# Power.net
KiCad netlist of a schematic drawn in Altium Designer
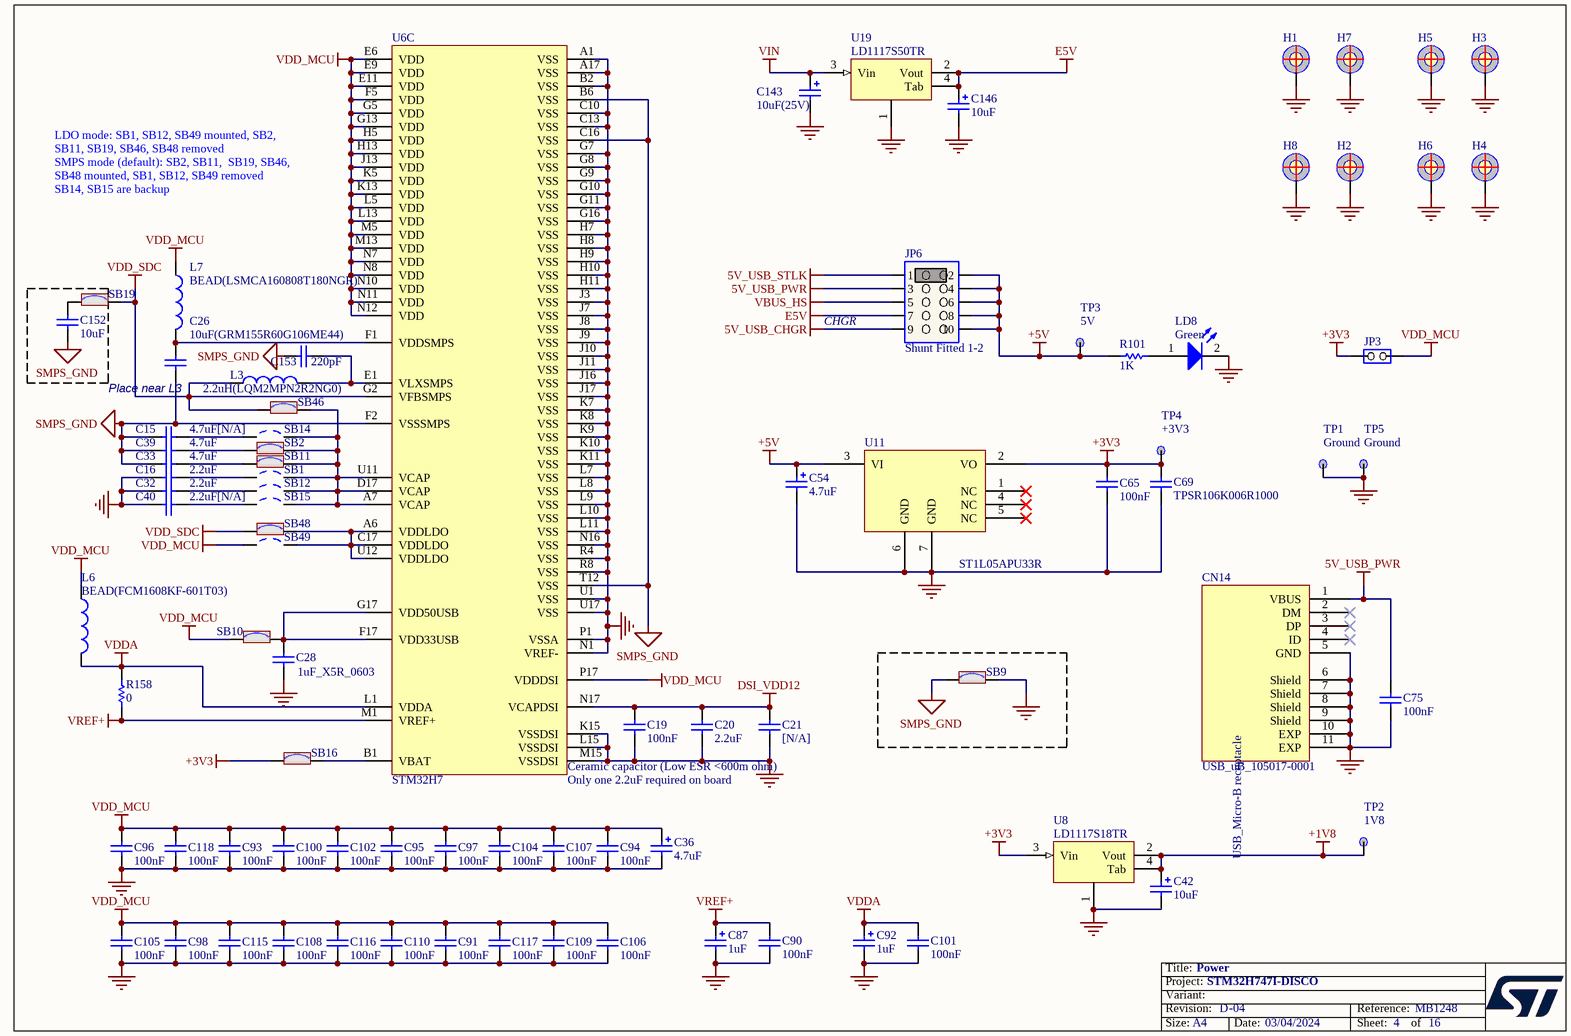
[diagram p0: Power.SchDoc]

(export (version "E")
  (design (tool "Eeschema 10.0.6"))
  (components
    (comp (ref "C15")
      (value "4.7uF[N/A]")
      (footprint "0402C")
      (description "Capacitor")
      (fields (field (name "PUBLISHER") "Altium Limited"))
      (libsource (lib "Miscellaneous Devices") (part "cap"))
    )
    (comp (ref "C16")
      (value "2.2uF")
      (footprint "0603C")
      (description "Capacitor")
      (fields (field (name "PUBLISHER") "Altium Limited"))
      (libsource (lib "Miscellaneous Devices") (part "Cap"))
    )
    (comp (ref "C19")
      (value "100nF")
      (footprint "0402C")
      (description "Capacitor")
      (fields (field (name "PUBLISHER") "Altium Limited"))
      (libsource (lib "Miscellaneous Devices") (part "CAP"))
    )
    (comp (ref "C20")
      (value "2.2uF")
      (footprint "0603C")
      (description "Capacitor")
      (fields (field (name "PUBLISHER") "Altium Limited"))
      (libsource (lib "Miscellaneous Devices") (part "CAP"))
    )
    (comp (ref "C21")
      (value "[N/A]")
      (footprint "1206C")
      (description "Capacitor")
      (fields (field (name "PUBLISHER") "Altium Limited"))
      (libsource (lib "Miscellaneous Devices") (part "cap"))
    )
    (comp (ref "C26")
      (value "10uF(GRM155R60G106ME44)")
      (footprint "0402C")
      (description "Capacitor")
      (fields (field (name "PUBLISHER") "Altium Limited"))
      (libsource (lib "Miscellaneous Devices") (part "Cap"))
    )
    (comp (ref "C28")
      (value "1uF_X5R_0603")
      (footprint "0603C")
      (description "0603  X5R 1礔")
      (fields (field (name "TOLERANCE") "10%"))
      (libsource (lib "MB963_1") (part "CAP SMD 0603  X5R 1礔 25V 10%"))
    )
    (comp (ref "C32")
      (value "2.2uF")
      (footprint "0603C")
      (description "Capacitor")
      (fields (field (name "PUBLISHER") "Altium Limited"))
      (libsource (lib "Miscellaneous Devices") (part "Cap"))
    )
    (comp (ref "C33")
      (value "4.7uF")
      (footprint "0402C")
      (description "Capacitor")
      (fields (field (name "PUBLISHER") "Altium Limited"))
      (libsource (lib "Miscellaneous Devices") (part "Cap"))
    )
    (comp (ref "C36")
      (value "4.7uF")
      (footprint "TAN-A")
      (description "Polarized Capacitor (Radial)")
      (fields (field (name "PUBLISHER") "Altium Limited"))
      (libsource (lib "Miscellaneous Devices") (part "Cap Pol1"))
    )
    (comp (ref "C39")
      (value "4.7uF")
      (footprint "0402C")
      (description "Capacitor")
      (fields (field (name "PUBLISHER") "Altium Limited"))
      (libsource (lib "Miscellaneous Devices") (part "Cap"))
    )
    (comp (ref "C40")
      (value "2.2uF[N/A]")
      (footprint "0603C")
      (description "Capacitor")
      (fields (field (name "PUBLISHER") "Altium Limited"))
      (libsource (lib "Miscellaneous Devices") (part "Cap"))
    )
    (comp (ref "C42")
      (value "10uF")
      (footprint "TAN-A")
      (description "Polarized Capacitor,10uF,10V,10%,typeA,VISHAY")
      (libsource (lib "MCD_TOOLS") (part "Cap_10uF_POL_10%_TANA"))
    )
    (comp (ref "C54")
      (value "4.7uF")
      (footprint "TAN-A")
      (description "Polarized Capacitor (Radial)")
      (fields (field (name "PUBLISHER") "Altium Limited"))
      (libsource (lib "*") (part "Cap Pol1"))
    )
    (comp (ref "C65")
      (value "100nF")
      (footprint "0603C")
      (description "Capacitor")
      (fields (field (name "PUBLISHER") "Altium Limited"))
      (libsource (lib "Miscellaneous Devices") (part "Cap"))
    )
    (comp (ref "C69")
      (value "TPSR106K006R1000")
      (footprint "0805C")
      (description "Capacitor")
      (libsource (lib "Miscellaneous Devices") (part "Cap"))
    )
    (comp (ref "C75")
      (value "100nF")
      (footprint "0402C")
      (description "Capacitor,20pF,50V,NPO,5%,0402")
      (fields
        (field (name "INTERNAL_PART_NUMBER") "MCD-00016")
        (field (name "MANUFACTURER_PART_NUMBER") "CC0402JRNPO9BN200")
        (field (name "PROVIDED_BY") "Subcon")
      )
      (libsource (lib "MCD_PARTS_database") (part "Capacitor"))
    )
    (comp (ref "C87")
      (value "1uF")
      (footprint "TAN-A")
      (description "Polarized Capacitor (Radial)")
      (fields (field (name "PUBLISHER") "Altium Limited"))
      (libsource (lib "Miscellaneous Devices") (part "Cap Pol1"))
    )
    (comp (ref "C90")
      (value "100nF")
      (footprint "0402C")
      (description "Capacitor")
      (fields (field (name "PUBLISHER") "Altium Limited"))
      (libsource (lib "Miscellaneous Devices") (part "Cap"))
    )
    (comp (ref "C91")
      (value "100nF")
      (footprint "0402C")
      (description "Capacitor")
      (fields (field (name "PUBLISHER") "Altium Limited"))
      (libsource (lib "Miscellaneous Devices") (part "CAP"))
    )
    (comp (ref "C92")
      (value "1uF")
      (footprint "TAN-A")
      (description "Polarized Capacitor (Radial)")
      (fields (field (name "PUBLISHER") "Altium Limited"))
      (libsource (lib "Miscellaneous Devices") (part "Cap Pol1"))
    )
    (comp (ref "C93")
      (value "100nF")
      (footprint "0402C")
      (description "Capacitor")
      (fields (field (name "PUBLISHER") "Altium Limited"))
      (libsource (lib "Miscellaneous Devices") (part "CAP"))
    )
    (comp (ref "C94")
      (value "100nF")
      (footprint "0402C")
      (description "Capacitor")
      (fields (field (name "PUBLISHER") "Altium Limited"))
      (libsource (lib "Miscellaneous Devices") (part "CAP"))
    )
    (comp (ref "C95")
      (value "100nF")
      (footprint "0402C")
      (description "Capacitor")
      (fields (field (name "PUBLISHER") "Altium Limited"))
      (libsource (lib "Miscellaneous Devices") (part "CAP"))
    )
    (comp (ref "C96")
      (value "100nF")
      (footprint "0402C")
      (description "Capacitor")
      (fields (field (name "PUBLISHER") "Altium Limited"))
      (libsource (lib "Miscellaneous Devices") (part "CAP"))
    )
    (comp (ref "C97")
      (value "100nF")
      (footprint "0402C")
      (description "Capacitor")
      (fields (field (name "PUBLISHER") "Altium Limited"))
      (libsource (lib "Miscellaneous Devices") (part "CAP"))
    )
    (comp (ref "C98")
      (value "100nF")
      (footprint "0402C")
      (description "Capacitor")
      (fields (field (name "PUBLISHER") "Altium Limited"))
      (libsource (lib "Miscellaneous Devices") (part "CAP"))
    )
    (comp (ref "C100")
      (value "100nF")
      (footprint "0402C")
      (description "Capacitor")
      (fields (field (name "PUBLISHER") "Altium Limited"))
      (libsource (lib "Miscellaneous Devices") (part "CAP"))
    )
    (comp (ref "C101")
      (value "100nF")
      (footprint "0402C")
      (description "Capacitor")
      (fields (field (name "PUBLISHER") "Altium Limited"))
      (libsource (lib "Miscellaneous Devices") (part "Cap"))
    )
    (comp (ref "C102")
      (value "100nF")
      (footprint "0402C")
      (description "Capacitor")
      (fields (field (name "PUBLISHER") "Altium Limited"))
      (libsource (lib "Miscellaneous Devices") (part "CAP"))
    )
    (comp (ref "C104")
      (value "100nF")
      (footprint "0402C")
      (description "Capacitor")
      (fields (field (name "PUBLISHER") "Altium Limited"))
      (libsource (lib "Miscellaneous Devices") (part "CAP"))
    )
    (comp (ref "C105")
      (value "100nF")
      (footprint "0402C")
      (description "Capacitor")
      (fields (field (name "PUBLISHER") "Altium Limited"))
      (libsource (lib "Miscellaneous Devices") (part "CAP"))
    )
    (comp (ref "C106")
      (value "100nF")
      (footprint "0402C")
      (description "Capacitor")
      (fields (field (name "PUBLISHER") "Altium Limited"))
      (libsource (lib "Miscellaneous Devices") (part "CAP"))
    )
    (comp (ref "C107")
      (value "100nF")
      (footprint "0402C")
      (description "Capacitor")
      (fields (field (name "PUBLISHER") "Altium Limited"))
      (libsource (lib "Miscellaneous Devices") (part "CAP"))
    )
    (comp (ref "C108")
      (value "100nF")
      (footprint "0402C")
      (description "Capacitor")
      (fields (field (name "PUBLISHER") "Altium Limited"))
      (libsource (lib "Miscellaneous Devices") (part "CAP"))
    )
    (comp (ref "C109")
      (value "100nF")
      (footprint "0402C")
      (description "Capacitor")
      (fields (field (name "PUBLISHER") "Altium Limited"))
      (libsource (lib "Miscellaneous Devices") (part "CAP"))
    )
    (comp (ref "C110")
      (value "100nF")
      (footprint "0402C")
      (description "Capacitor")
      (fields (field (name "PUBLISHER") "Altium Limited"))
      (libsource (lib "Miscellaneous Devices") (part "CAP"))
    )
    (comp (ref "C115")
      (value "100nF")
      (footprint "0402C")
      (description "Capacitor")
      (fields (field (name "PUBLISHER") "Altium Limited"))
      (libsource (lib "Miscellaneous Devices") (part "CAP"))
    )
    (comp (ref "C116")
      (value "100nF")
      (footprint "0402C")
      (description "Capacitor")
      (fields (field (name "PUBLISHER") "Altium Limited"))
      (libsource (lib "Miscellaneous Devices") (part "CAP"))
    )
    (comp (ref "C117")
      (value "100nF")
      (footprint "0402C")
      (description "Capacitor")
      (fields (field (name "PUBLISHER") "Altium Limited"))
      (libsource (lib "Miscellaneous Devices") (part "CAP"))
    )
    (comp (ref "C118")
      (value "100nF")
      (footprint "0402C")
      (description "Capacitor")
      (fields (field (name "PUBLISHER") "Altium Limited"))
      (libsource (lib "Miscellaneous Devices") (part "CAP"))
    )
    (comp (ref "C143")
      (value "10uF(25V)")
      (footprint "TAN-B")
      (description "Polarized Capacitor (Radial)")
      (fields (field (name "PUBLISHER") "Altium Limited"))
      (libsource (lib "Miscellaneous Devices") (part "Cap Pol1"))
    )
    (comp (ref "C146")
      (value "10uF")
      (footprint "TAN-A")
      (description "Polarized Capacitor,10uF,10V,10%,typeA,VISHAY")
      (libsource (lib "MCD_TOOLS") (part "Cap_10uF_POL_10%_TANA"))
    )
    (comp (ref "C152")
      (value "10uF")
      (footprint "0603C")
      (description "Capacitor")
      (fields (field (name "PUBLISHER") "Altium Limited"))
      (libsource (lib "Miscellaneous Devices") (part "Cap"))
    )
    (comp (ref "C153")
      (value "220pF")
      (footprint "0402C")
      (description "Capacitor")
      (fields (field (name "PUBLISHER") "Altium Limited"))
      (libsource (lib "Miscellaneous Devices") (part "Cap"))
    )
    (comp (ref "CN14")
      (value "USB_uB_105017-0001")
      (footprint "MICRO_USB_B_105017")
      (description "USB-MICRO-B, 0.65mm, RA, SMT, Bottom Mount,")
      (fields
        (field (name "INTERNAL_PART_NUMBER") "MCD-00028")
        (field (name "MANUFACTURER_PART_NUMBER") "1050170001")
        (field (name "PROVIDED_BY") "Subcon")
      )
      (libsource (lib "MCD_PARTS_database") (part "USB_uB_105017.0001"))
    )
    (comp (ref "H1")
      (value "POSITION HOLE C6D3R5")
      (footprint "HOLE_C7D3R5")
      (libsource (lib "MCD_TOOLS_MISCELLANEOUS") (part "POSITION HOLE C6D3R5"))
    )
    (comp (ref "H2")
      (value "POSITION HOLE C6D3R5")
      (footprint "HOLE_C7D3R5")
      (libsource (lib "MCD_TOOLS_MISCELLANEOUS") (part "POSITION HOLE C6D3R5"))
    )
    (comp (ref "H3")
      (value "POSITION HOLE C6D3R5")
      (footprint "HOLE_C9D4R5")
      (libsource (lib "MCD_TOOLS_MISCELLANEOUS") (part "POSITION HOLE C6D3R5"))
    )
    (comp (ref "H4")
      (value "POSITION HOLE C6D3R5")
      (footprint "HOLE_C9D4R5")
      (libsource (lib "MCD_TOOLS_MISCELLANEOUS") (part "POSITION HOLE C6D3R5"))
    )
    (comp (ref "H5")
      (value "POSITION HOLE C6D3R5")
      (footprint "HOLE_C9D4R5")
      (libsource (lib "MCD_TOOLS_MISCELLANEOUS") (part "POSITION HOLE C6D3R5"))
    )
    (comp (ref "H6")
      (value "POSITION HOLE C6D3R5")
      (footprint "HOLE_C9D4R5")
      (libsource (lib "MCD_TOOLS_MISCELLANEOUS") (part "POSITION HOLE C6D3R5"))
    )
    (comp (ref "H7")
      (value "POSITION HOLE C6D3R5")
      (footprint "HOLE_C7D3R5")
      (libsource (lib "MCD_TOOLS_MISCELLANEOUS") (part "POSITION HOLE C6D3R5"))
    )
    (comp (ref "H8")
      (value "POSITION HOLE C6D3R5")
      (footprint "HOLE_C7D3R5")
      (libsource (lib "MCD_TOOLS_MISCELLANEOUS") (part "POSITION HOLE C6D3R5"))
    )
    (comp (ref "JP3") (value "~") (footprint "SIP2") (libsource (lib "*") (part "JP2")))
    (comp (ref "JP6")
      (value "Shunt Fitted 1-2")
      (footprint "HDR_2X5_2R54")
      (description "Header, 5x2, 2,54mm, VR, TH, Height 5.84mm/2.54mm - Shunt Fitted 1-2")
      (fields
        (field (name "INTERNAL_PART_NUMBER") "MCD-01203")
        (field (name "MANUFACTURER_PART_NUMBER") "TSW-105-07-x-D")
        (field (name "PROVIDED_BY") "Subcon")
      )
      (libsource (lib "MCD_PARTS_database") (part "Jumper_Header 5x2 Fitted 1-2"))
    )
    (comp (ref "L3")
      (value "2.2uH(LQM2MPN2R2NG0)")
      (footprint "LSM2_VLS2016E_S")
      (description "Inductor")
      (fields (field (name "PUBLISHER") "Altium Limited"))
      (libsource (lib "Miscellaneous Devices") (part "Inductor"))
    )
    (comp (ref "L6")
      (value "BEAD(FCM1608KF-601T03)")
      (footprint "0603L")
      (description "Inductor")
      (fields (field (name "PUBLISHER") "Altium Limited"))
      (libsource (lib "Miscellaneous Devices") (part "Inductor"))
    )
    (comp (ref "L7")
      (value "BEAD(LSMCA160808T180NGR)")
      (footprint "0603L")
      (description "Inductor")
      (fields (field (name "MPN") "LSMCA160808T180NGR") (field (name "PUBLISHER") "Altium Limited"))
      (libsource (lib "Miscellaneous Devices") (part "Inductor"))
    )
    (comp (ref "LD8")
      (value "Green")
      (footprint "0603D")
      (description "Typical RED, GREEN, YELLOW, AMBER GaAs LED")
      (fields (field (name "PUBLISHER") "Altium Limited"))
      (libsource (lib "Miscellaneous Devices") (part "LED2"))
    )
    (comp (ref "R101")
      (value "1K")
      (footprint "0603R")
      (description "Resistor")
      (fields (field (name "PUBLISHER") "Altium Limited"))
      (libsource (lib "Miscellaneous Devices") (part "res1"))
    )
    (comp (ref "R158")
      (value "0")
      (footprint "0603R")
      (description "Resistor")
      (fields (field (name "PUBLISHER") "Altium Limited"))
      (libsource (lib "Miscellaneous Devices") (part "Res1"))
    )
    (comp (ref "SB1")
      (value "Solder Bridge OFF")
      (footprint "SB_0603")
      (libsource (lib "MCD_TOOLS") (part "SB_OFF"))
    )
    (comp (ref "SB2")
      (value "Solder Bridge ON")
      (footprint "SB_0603")
      (libsource (lib "MCD_TOOLS") (part "SB_ON"))
    )
    (comp (ref "SB9")
      (value "Solder Bridge ON")
      (footprint "SB_0603")
      (libsource (lib "MCD_TOOLS") (part "SB_ON"))
    )
    (comp (ref "SB10")
      (value "Solder Bridge ON")
      (footprint "SB_0603")
      (libsource (lib "MCD_TOOLS") (part "SB_ON"))
    )
    (comp (ref "SB11")
      (value "Solder Bridge ON")
      (footprint "SB_0603")
      (libsource (lib "MCD_TOOLS") (part "SB_ON"))
    )
    (comp (ref "SB12")
      (value "Solder Bridge OFF")
      (footprint "SB_0603")
      (libsource (lib "MCD_TOOLS") (part "SB_OFF"))
    )
    (comp (ref "SB14")
      (value "Solder Bridge OFF")
      (footprint "SB_0603")
      (libsource (lib "MCD_TOOLS") (part "SB_OFF"))
    )
    (comp (ref "SB15")
      (value "Solder Bridge OFF")
      (footprint "SB_0603")
      (libsource (lib "MCD_TOOLS") (part "SB_OFF"))
    )
    (comp (ref "SB16")
      (value "Solder Bridge ON")
      (footprint "SB_0603")
      (libsource (lib "MCD_TOOLS") (part "SB_ON"))
    )
    (comp (ref "SB19")
      (value "Solder Bridge ON")
      (footprint "SB_0603")
      (libsource (lib "MCD_TOOLS") (part "SB_ON"))
    )
    (comp (ref "SB46")
      (value "Solder Bridge ON")
      (footprint "SB_0603")
      (libsource (lib "MCD_TOOLS") (part "SB_ON"))
    )
    (comp (ref "SB48")
      (value "Solder Bridge ON")
      (footprint "SB_0603")
      (libsource (lib "MCD_TOOLS") (part "SB_ON"))
    )
    (comp (ref "SB49")
      (value "Solder Bridge OFF")
      (footprint "SB_0603")
      (libsource (lib "MCD_TOOLS") (part "SB_OFF"))
    )
    (comp (ref "TP1") (value "Ground") (footprint "TP_C40") (libsource (lib "*") (part "TP")))
    (comp (ref "TP2") (value "1V8") (footprint "TP_C40") (libsource (lib "*") (part "TP")))
    (comp (ref "TP3") (value "5V") (footprint "TP_C40") (libsource (lib "*") (part "TP")))
    (comp (ref "TP4") (value "+3V3") (footprint "TP_C40") (libsource (lib "*") (part "TP")))
    (comp (ref "TP5") (value "Ground") (footprint "TP_C40") (libsource (lib "*") (part "TP")))
    (comp (ref "U6")
      (value "STM32H7")
      (footprint "BGA265_0R8_14X14_SKT")
      (libsource (lib "MB1246") (part "STM32H7_TFBGA265"))
    )
    (comp (ref "U8") (value "LD1117S18TR") (footprint "SOT-223") (libsource (lib "mb1045") (part "LD1117")))
    (comp (ref "U11")
      (value "ST1L05APU33R")
      (footprint "DFN6_0R95_3X3")
      (libsource (lib "MB1248") (part "ST1L05A"))
    )
    (comp (ref "U19") (value "LD1117S50TR") (footprint "SOT-223") (libsource (lib "mb1045") (part "LD1117")))
  )
  (nets
    (net (code "1") (name "+1V8") (class "Default")
      (node (ref "C42") (pin "1") (pinfunction "1_1") (pintype "passive"))
      (node (ref "TP2") (pin "1") (pinfunction "1_1") (pintype "passive"))
      (node (ref "U8") (pin "2") (pinfunction "Vout_2") (pintype "power_in"))
      (node (ref "U8") (pin "4") (pinfunction "Tab_4") (pintype "power_in"))
    )
    (net (code "2") (name "+3V3") (class "Default")
      (node (ref "C65") (pin "1") (pinfunction "1_1") (pintype "passive"))
      (node (ref "C69") (pin "2") (pinfunction "2_2") (pintype "passive"))
      (node (ref "JP3") (pin "1") (pinfunction "COMMON_1") (pintype "passive"))
      (node (ref "SB16") (pin "1") (pinfunction "1_1") (pintype "passive"))
      (node (ref "TP4") (pin "1") (pinfunction "1_1") (pintype "passive"))
      (node (ref "U11") (pin "2") (pinfunction "VO_2") (pintype "passive"))
      (node (ref "U8") (pin "3") (pinfunction "Vin_3") (pintype "input"))
    )
    (net (code "3") (name "+5V") (class "Default")
      (node (ref "C54") (pin "1") (pinfunction "1_1") (pintype "passive"))
      (node (ref "JP6") (pin "10") (pinfunction "10_10") (pintype "passive"))
      (node (ref "JP6") (pin "2") (pinfunction "2_2") (pintype "passive"))
      (node (ref "JP6") (pin "4") (pinfunction "4_4") (pintype "passive"))
      (node (ref "JP6") (pin "6") (pinfunction "6_6") (pintype "passive"))
      (node (ref "JP6") (pin "8") (pinfunction "8_8") (pintype "passive"))
      (node (ref "R101") (pin "2") (pinfunction "2_2") (pintype "passive"))
      (node (ref "TP3") (pin "1") (pinfunction "1_1") (pintype "passive"))
      (node (ref "U11") (pin "3") (pinfunction "VI_3") (pintype "passive"))
    )
    (net (code "4") (name "5V_USB_CHGR") (class "Default")
      (node (ref "JP6") (pin "9") (pinfunction "9_9") (pintype "passive"))
    )
    (net (code "5") (name "5V_USB_PWR") (class "Default")
      (node (ref "C75") (pin "2") (pinfunction "2_2") (pintype "passive"))
      (node (ref "CN14") (pin "1") (pinfunction "VBUS_1") (pintype "passive"))
      (node (ref "JP6") (pin "3") (pinfunction "3_3") (pintype "passive"))
    )
    (net (code "6") (name "5V_USB_STLK") (class "Default")
      (node (ref "JP6") (pin "1") (pinfunction "1_1") (pintype "passive"))
    )
    (net (code "7") (name "DSI_VDD12") (class "Default")
      (node (ref "C19") (pin "1") (pinfunction "1_1") (pintype "passive"))
      (node (ref "C20") (pin "1") (pinfunction "1_1") (pintype "passive"))
      (node (ref "C21") (pin "2") (pinfunction "2_2") (pintype "passive"))
      (node (ref "U6") (pin "N17") (pinfunction "VCAPDSI_N17") (pintype "passive"))
    )
    (net (code "8") (name "E5V") (class "Default")
      (node (ref "C146") (pin "1") (pinfunction "1_1") (pintype "passive"))
      (node (ref "JP6") (pin "7") (pinfunction "7_7") (pintype "passive"))
      (node (ref "U19") (pin "2") (pinfunction "Vout_2") (pintype "power_in"))
      (node (ref "U19") (pin "4") (pinfunction "Tab_4") (pintype "power_in"))
    )
    (net (code "9") (name "GND") (class "Default")
      (node (ref "C100") (pin "2") (pinfunction "2_2") (pintype "passive"))
      (node (ref "C101") (pin "1") (pinfunction "1_1") (pintype "passive"))
      (node (ref "C102") (pin "2") (pinfunction "2_2") (pintype "passive"))
      (node (ref "C104") (pin "2") (pinfunction "2_2") (pintype "passive"))
      (node (ref "C105") (pin "2") (pinfunction "2_2") (pintype "passive"))
      (node (ref "C106") (pin "2") (pinfunction "2_2") (pintype "passive"))
      (node (ref "C107") (pin "2") (pinfunction "2_2") (pintype "passive"))
      (node (ref "C108") (pin "2") (pinfunction "2_2") (pintype "passive"))
      (node (ref "C109") (pin "2") (pinfunction "2_2") (pintype "passive"))
      (node (ref "C110") (pin "2") (pinfunction "2_2") (pintype "passive"))
      (node (ref "C115") (pin "2") (pinfunction "2_2") (pintype "passive"))
      (node (ref "C116") (pin "2") (pinfunction "2_2") (pintype "passive"))
      (node (ref "C117") (pin "2") (pinfunction "2_2") (pintype "passive"))
      (node (ref "C118") (pin "2") (pinfunction "2_2") (pintype "passive"))
      (node (ref "C143") (pin "2") (pinfunction "2_2") (pintype "passive"))
      (node (ref "C146") (pin "2") (pinfunction "2_2") (pintype "passive"))
      (node (ref "C16") (pin "1") (pinfunction "1_1") (pintype "passive"))
      (node (ref "C19") (pin "2") (pinfunction "2_2") (pintype "passive"))
      (node (ref "C20") (pin "2") (pinfunction "2_2") (pintype "passive"))
      (node (ref "C21") (pin "1") (pinfunction "1_1") (pintype "passive"))
      (node (ref "C28") (pin "1") (pinfunction "1_1") (pintype "passive"))
      (node (ref "C32") (pin "1") (pinfunction "1_1") (pintype "passive"))
      (node (ref "C36") (pin "2") (pinfunction "2_2") (pintype "passive"))
      (node (ref "C40") (pin "1") (pinfunction "1_1") (pintype "passive"))
      (node (ref "C42") (pin "2") (pinfunction "2_2") (pintype "passive"))
      (node (ref "C54") (pin "2") (pinfunction "2_2") (pintype "passive"))
      (node (ref "C65") (pin "2") (pinfunction "2_2") (pintype "passive"))
      (node (ref "C69") (pin "1") (pinfunction "1_1") (pintype "passive"))
      (node (ref "C75") (pin "1") (pinfunction "1_1") (pintype "passive"))
      (node (ref "C87") (pin "2") (pinfunction "2_2") (pintype "passive"))
      (node (ref "C90") (pin "1") (pinfunction "1_1") (pintype "passive"))
      (node (ref "C91") (pin "2") (pinfunction "2_2") (pintype "passive"))
      (node (ref "C92") (pin "2") (pinfunction "2_2") (pintype "passive"))
      (node (ref "C93") (pin "2") (pinfunction "2_2") (pintype "passive"))
      (node (ref "C94") (pin "2") (pinfunction "2_2") (pintype "passive"))
      (node (ref "C95") (pin "2") (pinfunction "2_2") (pintype "passive"))
      (node (ref "C96") (pin "2") (pinfunction "2_2") (pintype "passive"))
      (node (ref "C97") (pin "2") (pinfunction "2_2") (pintype "passive"))
      (node (ref "C98") (pin "2") (pinfunction "2_2") (pintype "passive"))
      (node (ref "CN14") (pin "10") (pinfunction "EXP_10") (pintype "passive"))
      (node (ref "CN14") (pin "11") (pinfunction "EXP_11") (pintype "passive"))
      (node (ref "CN14") (pin "5") (pinfunction "GND_5") (pintype "passive"))
      (node (ref "CN14") (pin "6") (pinfunction "Shield_6") (pintype "passive"))
      (node (ref "CN14") (pin "7") (pinfunction "Shield_7") (pintype "passive"))
      (node (ref "CN14") (pin "8") (pinfunction "Shield_8") (pintype "passive"))
      (node (ref "CN14") (pin "9") (pinfunction "Shield_9") (pintype "passive"))
      (node (ref "H1") (pin "1") (pinfunction "1_1") (pintype "passive"))
      (node (ref "H2") (pin "1") (pinfunction "1_1") (pintype "passive"))
      (node (ref "H3") (pin "1") (pinfunction "1_1") (pintype "passive"))
      (node (ref "H4") (pin "1") (pinfunction "1_1") (pintype "passive"))
      (node (ref "H5") (pin "1") (pinfunction "1_1") (pintype "passive"))
      (node (ref "H6") (pin "1") (pinfunction "1_1") (pintype "passive"))
      (node (ref "H7") (pin "1") (pinfunction "1_1") (pintype "passive"))
      (node (ref "H8") (pin "1") (pinfunction "1_1") (pintype "passive"))
      (node (ref "LD8") (pin "2") (pinfunction "K_2") (pintype "passive"))
      (node (ref "SB9") (pin "2") (pinfunction "2_2") (pintype "passive"))
      (node (ref "TP1") (pin "1") (pinfunction "1_1") (pintype "passive"))
      (node (ref "TP5") (pin "1") (pinfunction "1_1") (pintype "passive"))
      (node (ref "U11") (pin "6") (pinfunction "GND_6") (pintype "passive"))
      (node (ref "U11") (pin "7") (pinfunction "GND_7") (pintype "passive"))
      (node (ref "U19") (pin "1") (pintype "passive"))
      (node (ref "U6") (pin "A1") (pinfunction "VSS_A1") (pintype "passive"))
      (node (ref "U6") (pin "A17") (pinfunction "VSS_A17") (pintype "passive"))
      (node (ref "U6") (pin "B2") (pinfunction "VSS_B2") (pintype "passive"))
      (node (ref "U6") (pin "C10") (pinfunction "VSS_C10") (pintype "passive"))
      (node (ref "U6") (pin "C13") (pinfunction "VSS_C13") (pintype "passive"))
      (node (ref "U6") (pin "G10") (pinfunction "VSS_G10") (pintype "passive"))
      (node (ref "U6") (pin "G11") (pinfunction "VSS_G11") (pintype "passive"))
      (node (ref "U6") (pin "G16") (pinfunction "VSS_G16") (pintype "passive"))
      (node (ref "U6") (pin "G7") (pinfunction "VSS_G7") (pintype "passive"))
      (node (ref "U6") (pin "G8") (pinfunction "VSS_G8") (pintype "passive"))
      (node (ref "U6") (pin "G9") (pinfunction "VSS_G9") (pintype "passive"))
      (node (ref "U6") (pin "H10") (pinfunction "VSS_H10") (pintype "passive"))
      (node (ref "U6") (pin "H11") (pinfunction "VSS_H11") (pintype "passive"))
      (node (ref "U6") (pin "H7") (pinfunction "VSS_H7") (pintype "passive"))
      (node (ref "U6") (pin "H8") (pinfunction "VSS_H8") (pintype "passive"))
      (node (ref "U6") (pin "H9") (pinfunction "VSS_H9") (pintype "passive"))
      (node (ref "U6") (pin "J10") (pinfunction "VSS_J10") (pintype "passive"))
      (node (ref "U6") (pin "J11") (pinfunction "VSS_J11") (pintype "passive"))
      (node (ref "U6") (pin "J16") (pinfunction "VSS_J16") (pintype "passive"))
      (node (ref "U6") (pin "J17") (pinfunction "VSS_J17") (pintype "passive"))
      (node (ref "U6") (pin "J3") (pinfunction "VSS_J3") (pintype "passive"))
      (node (ref "U6") (pin "J7") (pinfunction "VSS_J7") (pintype "passive"))
      (node (ref "U6") (pin "J8") (pinfunction "VSS_J8") (pintype "passive"))
      (node (ref "U6") (pin "J9") (pinfunction "VSS_J9") (pintype "passive"))
      (node (ref "U6") (pin "K10") (pinfunction "VSS_K10") (pintype "passive"))
      (node (ref "U6") (pin "K11") (pinfunction "VSS_K11") (pintype "passive"))
      (node (ref "U6") (pin "K15") (pinfunction "VSSDSI_K15") (pintype "passive"))
      (node (ref "U6") (pin "K7") (pinfunction "VSS_K7") (pintype "passive"))
      (node (ref "U6") (pin "K8") (pinfunction "VSS_K8") (pintype "passive"))
      (node (ref "U6") (pin "K9") (pinfunction "VSS_K9") (pintype "passive"))
      (node (ref "U6") (pin "L10") (pinfunction "VSS_L10") (pintype "passive"))
      (node (ref "U6") (pin "L11") (pinfunction "VSS_L11") (pintype "passive"))
      (node (ref "U6") (pin "L15") (pinfunction "VSSDSI_L15") (pintype "passive"))
      (node (ref "U6") (pin "L7") (pinfunction "VSS_L7") (pintype "passive"))
      (node (ref "U6") (pin "L8") (pinfunction "VSS_L8") (pintype "passive"))
      (node (ref "U6") (pin "L9") (pinfunction "VSS_L9") (pintype "passive"))
      (node (ref "U6") (pin "M15") (pinfunction "VSSDSI_M15") (pintype "passive"))
      (node (ref "U6") (pin "N1") (pinfunction "VREF-_N1") (pintype "passive"))
      (node (ref "U6") (pin "N16") (pinfunction "VSS_N16") (pintype "passive"))
      (node (ref "U6") (pin "P1") (pinfunction "VSSA_P1") (pintype "passive"))
      (node (ref "U6") (pin "R4") (pinfunction "VSS_R4") (pintype "passive"))
      (node (ref "U6") (pin "R8") (pinfunction "VSS_R8") (pintype "passive"))
      (node (ref "U6") (pin "U1") (pinfunction "VSS_U1") (pintype "passive"))
      (node (ref "U6") (pin "U17") (pinfunction "VSS_U17") (pintype "passive"))
      (node (ref "U8") (pin "1") (pintype "passive"))
    )
    (net (code "10") (name "Net-(C15-Pad2)") (class "Default")
      (node (ref "C15") (pin "2") (pinfunction "2_2") (pintype "passive"))
      (node (ref "SB14") (pin "1") (pinfunction "1_1") (pintype "passive"))
    )
    (net (code "11") (name "Net-(C16-Pad2)") (class "Default")
      (node (ref "C16") (pin "2") (pinfunction "2_2") (pintype "passive"))
      (node (ref "SB1") (pin "1") (pinfunction "1_1") (pintype "passive"))
    )
    (net (code "12") (name "Net-(C32-Pad2)") (class "Default")
      (node (ref "C32") (pin "2") (pinfunction "2_2") (pintype "passive"))
      (node (ref "SB12") (pin "1") (pinfunction "1_1") (pintype "passive"))
    )
    (net (code "13") (name "Net-(C33-Pad2)") (class "Default")
      (node (ref "C33") (pin "2") (pinfunction "2_2") (pintype "passive"))
      (node (ref "SB11") (pin "1") (pinfunction "1_1") (pintype "passive"))
    )
    (net (code "14") (name "Net-(C39-Pad2)") (class "Default")
      (node (ref "C39") (pin "2") (pinfunction "2_2") (pintype "passive"))
      (node (ref "SB2") (pin "1") (pinfunction "1_1") (pintype "passive"))
    )
    (net (code "15") (name "Net-(C40-Pad2)") (class "Default")
      (node (ref "C40") (pin "2") (pinfunction "2_2") (pintype "passive"))
      (node (ref "SB15") (pin "1") (pinfunction "1_1") (pintype "passive"))
    )
    (net (code "16") (name "Net-(C152-Pad2)") (class "Default")
      (node (ref "C152") (pin "2") (pinfunction "2_2") (pintype "passive"))
      (node (ref "SB19") (pin "1") (pinfunction "1_1") (pintype "passive"))
    )
    (net (code "17") (name "Net-(LD8-A)") (class "Default")
      (node (ref "LD8") (pin "1") (pinfunction "A_1") (pintype "passive"))
      (node (ref "R101") (pin "1") (pinfunction "1_1") (pintype "passive"))
    )
    (net (code "18") (name "Net-(SB1-Pad2)") (class "Default")
      (node (ref "SB1") (pin "2") (pinfunction "2_2") (pintype "passive"))
      (node (ref "SB11") (pin "2") (pinfunction "2_2") (pintype "passive"))
      (node (ref "SB12") (pin "2") (pinfunction "2_2") (pintype "passive"))
      (node (ref "SB14") (pin "2") (pinfunction "2_2") (pintype "passive"))
      (node (ref "SB15") (pin "2") (pinfunction "2_2") (pintype "passive"))
      (node (ref "SB2") (pin "2") (pinfunction "2_2") (pintype "passive"))
      (node (ref "SB46") (pin "2") (pinfunction "2_2") (pintype "passive"))
      (node (ref "U6") (pin "A7") (pinfunction "VCAP_A7") (pintype "passive"))
      (node (ref "U6") (pin "D17") (pinfunction "VCAP_D17") (pintype "passive"))
      (node (ref "U6") (pin "U11") (pinfunction "VCAP_U11") (pintype "passive"))
    )
    (net (code "19") (name "Net-(SB48-Pad2)") (class "Default")
      (node (ref "SB48") (pin "2") (pinfunction "2_2") (pintype "passive"))
      (node (ref "SB49") (pin "2") (pinfunction "2_2") (pintype "passive"))
      (node (ref "U6") (pin "A6") (pinfunction "VDDLDO_A6") (pintype "passive"))
      (node (ref "U6") (pin "C17") (pinfunction "VDDLDO_C17") (pintype "passive"))
      (node (ref "U6") (pin "U12") (pinfunction "VDDLDO_U12") (pintype "passive"))
    )
    (net (code "20") (name "Net-(U6C-VBAT)") (class "Default")
      (node (ref "SB16") (pin "2") (pinfunction "2_2") (pintype "passive"))
      (node (ref "U6") (pin "B1") (pinfunction "VBAT_B1") (pintype "passive"))
    )
    (net (code "21") (name "Net-(U6C-VDD33USB)") (class "Default")
      (node (ref "C28") (pin "2") (pinfunction "2_2") (pintype "passive"))
      (node (ref "SB10") (pin "2") (pinfunction "2_2") (pintype "passive"))
      (node (ref "U6") (pin "F17") (pinfunction "VDD33USB_F17") (pintype "passive"))
      (node (ref "U6") (pin "G17") (pinfunction "VDD50USB_G17") (pintype "passive"))
    )
    (net (code "22") (name "Net-(U6C-VDDSMPS)") (class "Default")
      (node (ref "C26") (pin "2") (pinfunction "2_2") (pintype "passive"))
      (node (ref "L7") (pin "2") (pinfunction "2_2") (pintype "passive"))
      (node (ref "U6") (pin "F1") (pinfunction "VDDSMPS_F1") (pintype "passive"))
    )
    (net (code "23") (name "Net-(U6C-VLXSMPS)") (class "Default")
      (node (ref "C153") (pin "1") (pinfunction "1_1") (pintype "passive"))
      (node (ref "L3") (pin "2") (pinfunction "2_2") (pintype "passive"))
      (node (ref "U6") (pin "E1") (pinfunction "VLXSMPS_E1") (pintype "passive"))
    )
    (net (code "24") (name "SMPS_GND") (class "Default")
      (node (ref "C15") (pin "1") (pinfunction "1_1") (pintype "passive"))
      (node (ref "C152") (pin "1") (pinfunction "1_1") (pintype "passive"))
      (node (ref "C153") (pin "2") (pinfunction "2_2") (pintype "passive"))
      (node (ref "C26") (pin "1") (pinfunction "1_1") (pintype "passive"))
      (node (ref "C33") (pin "1") (pinfunction "1_1") (pintype "passive"))
      (node (ref "C39") (pin "1") (pinfunction "1_1") (pintype "passive"))
      (node (ref "SB9") (pin "1") (pinfunction "1_1") (pintype "passive"))
      (node (ref "U6") (pin "B6") (pinfunction "VSS_B6") (pintype "passive"))
      (node (ref "U6") (pin "C16") (pinfunction "VSS_C16") (pintype "passive"))
      (node (ref "U6") (pin "F2") (pinfunction "VSSSMPS_F2") (pintype "passive"))
      (node (ref "U6") (pin "T12") (pinfunction "VSS_T12") (pintype "passive"))
    )
    (net (code "25") (name "VBUS_HS") (class "Default")
      (node (ref "JP6") (pin "5") (pinfunction "5_5") (pintype "passive"))
    )
    (net (code "26") (name "VDDA") (class "Default")
      (node (ref "C101") (pin "2") (pinfunction "2_2") (pintype "passive"))
      (node (ref "C92") (pin "1") (pinfunction "1_1") (pintype "passive"))
      (node (ref "L6") (pin "2") (pinfunction "2_2") (pintype "passive"))
      (node (ref "R158") (pin "1") (pinfunction "1_1") (pintype "passive"))
      (node (ref "U6") (pin "L1") (pinfunction "VDDA_L1") (pintype "passive"))
    )
    (net (code "27") (name "VDD_MCU") (class "Default")
      (node (ref "C100") (pin "1") (pinfunction "1_1") (pintype "passive"))
      (node (ref "C102") (pin "1") (pinfunction "1_1") (pintype "passive"))
      (node (ref "C104") (pin "1") (pinfunction "1_1") (pintype "passive"))
      (node (ref "C105") (pin "1") (pinfunction "1_1") (pintype "passive"))
      (node (ref "C106") (pin "1") (pinfunction "1_1") (pintype "passive"))
      (node (ref "C107") (pin "1") (pinfunction "1_1") (pintype "passive"))
      (node (ref "C108") (pin "1") (pinfunction "1_1") (pintype "passive"))
      (node (ref "C109") (pin "1") (pinfunction "1_1") (pintype "passive"))
      (node (ref "C110") (pin "1") (pinfunction "1_1") (pintype "passive"))
      (node (ref "C115") (pin "1") (pinfunction "1_1") (pintype "passive"))
      (node (ref "C116") (pin "1") (pinfunction "1_1") (pintype "passive"))
      (node (ref "C117") (pin "1") (pinfunction "1_1") (pintype "passive"))
      (node (ref "C118") (pin "1") (pinfunction "1_1") (pintype "passive"))
      (node (ref "C36") (pin "1") (pinfunction "1_1") (pintype "passive"))
      (node (ref "C91") (pin "1") (pinfunction "1_1") (pintype "passive"))
      (node (ref "C93") (pin "1") (pinfunction "1_1") (pintype "passive"))
      (node (ref "C94") (pin "1") (pinfunction "1_1") (pintype "passive"))
      (node (ref "C95") (pin "1") (pinfunction "1_1") (pintype "passive"))
      (node (ref "C96") (pin "1") (pinfunction "1_1") (pintype "passive"))
      (node (ref "C97") (pin "1") (pinfunction "1_1") (pintype "passive"))
      (node (ref "C98") (pin "1") (pinfunction "1_1") (pintype "passive"))
      (node (ref "JP3") (pin "2") (pinfunction "NO_2") (pintype "passive"))
      (node (ref "L6") (pin "1") (pinfunction "1_1") (pintype "passive"))
      (node (ref "L7") (pin "1") (pinfunction "1_1") (pintype "passive"))
      (node (ref "SB10") (pin "1") (pinfunction "1_1") (pintype "passive"))
      (node (ref "SB49") (pin "1") (pinfunction "1_1") (pintype "passive"))
      (node (ref "U6") (pin "E11") (pinfunction "VDD_E11") (pintype "passive"))
      (node (ref "U6") (pin "E6") (pinfunction "VDD_E6") (pintype "passive"))
      (node (ref "U6") (pin "E9") (pinfunction "VDD_E9") (pintype "passive"))
      (node (ref "U6") (pin "F5") (pinfunction "VDD_F5") (pintype "passive"))
      (node (ref "U6") (pin "G13") (pinfunction "VDD_G13") (pintype "passive"))
      (node (ref "U6") (pin "G5") (pinfunction "VDD_G5") (pintype "passive"))
      (node (ref "U6") (pin "H13") (pinfunction "VDD_H13") (pintype "passive"))
      (node (ref "U6") (pin "H5") (pinfunction "VDD_H5") (pintype "passive"))
      (node (ref "U6") (pin "J13") (pinfunction "VDD_J13") (pintype "passive"))
      (node (ref "U6") (pin "K13") (pinfunction "VDD_K13") (pintype "passive"))
      (node (ref "U6") (pin "K5") (pinfunction "VDD_K5") (pintype "passive"))
      (node (ref "U6") (pin "L13") (pinfunction "VDD_L13") (pintype "passive"))
      (node (ref "U6") (pin "L5") (pinfunction "VDD_L5") (pintype "passive"))
      (node (ref "U6") (pin "M13") (pinfunction "VDD_M13") (pintype "passive"))
      (node (ref "U6") (pin "M5") (pinfunction "VDD_M5") (pintype "passive"))
      (node (ref "U6") (pin "N10") (pinfunction "VDD_N10") (pintype "passive"))
      (node (ref "U6") (pin "N11") (pinfunction "VDD_N11") (pintype "passive"))
      (node (ref "U6") (pin "N12") (pinfunction "VDD_N12") (pintype "passive"))
      (node (ref "U6") (pin "N7") (pinfunction "VDD_N7") (pintype "passive"))
      (node (ref "U6") (pin "N8") (pinfunction "VDD_N8") (pintype "passive"))
      (node (ref "U6") (pin "P17") (pinfunction "VDDDSI_P17") (pintype "passive"))
    )
    (net (code "28") (name "VDD_SDC") (class "Default")
      (node (ref "L3") (pin "1") (pinfunction "1_1") (pintype "passive"))
      (node (ref "SB19") (pin "2") (pinfunction "2_2") (pintype "passive"))
      (node (ref "SB46") (pin "1") (pinfunction "1_1") (pintype "passive"))
      (node (ref "SB48") (pin "1") (pinfunction "1_1") (pintype "passive"))
      (node (ref "U6") (pin "G2") (pinfunction "VFBSMPS_G2") (pintype "passive"))
    )
    (net (code "29") (name "VIN") (class "Default")
      (node (ref "C143") (pin "1") (pinfunction "1_1") (pintype "passive"))
      (node (ref "U19") (pin "3") (pinfunction "Vin_3") (pintype "input"))
    )
    (net (code "30") (name "VREF+") (class "Default")
      (node (ref "C87") (pin "1") (pinfunction "1_1") (pintype "passive"))
      (node (ref "C90") (pin "2") (pinfunction "2_2") (pintype "passive"))
      (node (ref "R158") (pin "2") (pinfunction "2_2") (pintype "passive"))
      (node (ref "U6") (pin "M1") (pinfunction "VREF+_M1") (pintype "passive"))
    )
    (net (code "31") (name "unconnected-(CN14-DM-Pad2)") (class "Default")
      (node (ref "CN14") (pin "2") (pinfunction "DM_2") (pintype "passive+no_connect"))
    )
    (net (code "32") (name "unconnected-(CN14-DP-Pad3)") (class "Default")
      (node (ref "CN14") (pin "3") (pinfunction "DP_3") (pintype "passive+no_connect"))
    )
    (net (code "33") (name "unconnected-(CN14-ID-Pad4)") (class "Default")
      (node (ref "CN14") (pin "4") (pinfunction "ID_4") (pintype "passive+no_connect"))
    )
    (net (code "34") (name "unconnected-(U11-NC-Pad1)") (class "Default")
      (node (ref "U11") (pin "1") (pinfunction "NC_1") (pintype "passive+no_connect"))
    )
    (net (code "35") (name "unconnected-(U11-NC-Pad4)") (class "Default")
      (node (ref "U11") (pin "4") (pinfunction "NC_4") (pintype "passive+no_connect"))
    )
    (net (code "36") (name "unconnected-(U11-NC-Pad5)") (class "Default")
      (node (ref "U11") (pin "5") (pinfunction "NC_5") (pintype "passive+no_connect"))
    )
  )
)
